# TheStaticTurtle_oshw-sdi3g-fiber__schema.net
KiCad netlist of a schematic drawn in Altium Designer
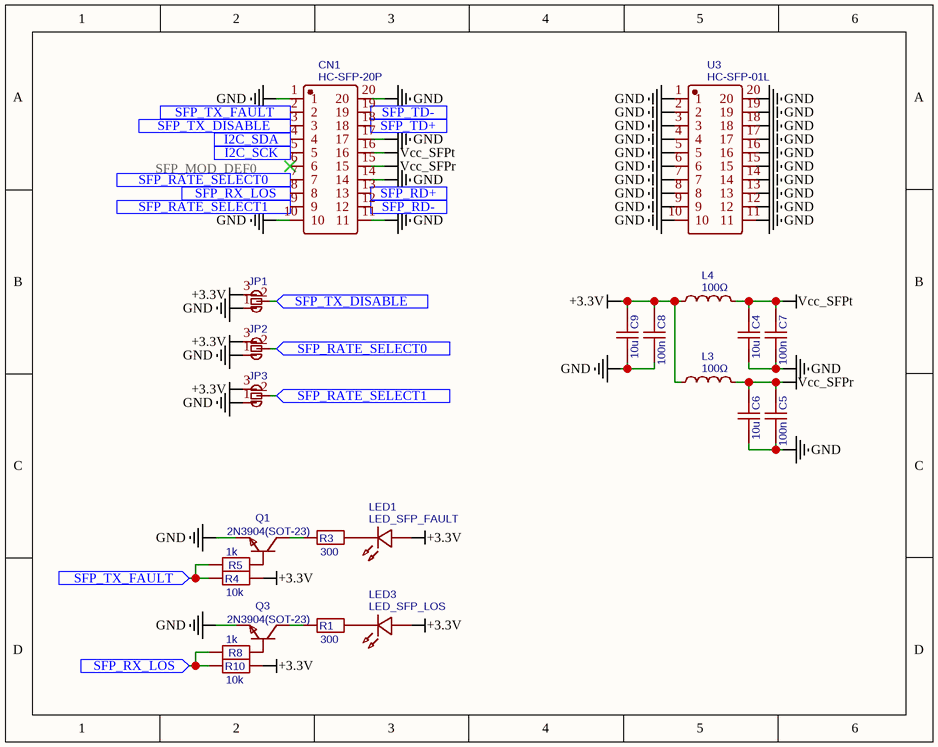
[diagram p0: TheStaticTurtle_oshw-sdi3g-fiber__schematic_V4-Reclocked_OSHW_BiDi_SDI_Fiber_Converter_V4_Reclocker_2024-11-17__SFP.schdoc]

(export (version "E")
  (design (tool "Eeschema 10.0.6"))
  (components
    (comp (ref "C4")
      (value "10u")
      (fields (field (name "CONTRIBUTOR") "LCEDA_Lib"))
      (libsource (lib "altium-import") (part "root_1_10u_"))
    )
    (comp (ref "C5")
      (value "100n")
      (fields (field (name "CONTRIBUTOR") "LCEDA_Lib"))
      (libsource (lib "altium-import") (part "root_1_100n_"))
    )
    (comp (ref "C6")
      (value "10u")
      (fields (field (name "CONTRIBUTOR") "LCEDA_Lib"))
      (libsource (lib "altium-import") (part "root_1_10u_"))
    )
    (comp (ref "C7")
      (value "100n")
      (fields (field (name "CONTRIBUTOR") "LCEDA_Lib"))
      (libsource (lib "altium-import") (part "root_1_100n_"))
    )
    (comp (ref "C8")
      (value "100n")
      (fields (field (name "CONTRIBUTOR") "LCEDA_Lib"))
      (libsource (lib "altium-import") (part "root_1_100n_"))
    )
    (comp (ref "C9")
      (value "10u")
      (fields (field (name "CONTRIBUTOR") "LCEDA_Lib"))
      (libsource (lib "altium-import") (part "root_1_10u_"))
    )
    (comp (ref "CN1")
      (value "HC-SFP-20P")
      (fields (field (name "MANUFACTURER") "HCTL(华灿天禄)") (field (name "CONTRIBUTOR") "LCSC"))
      (libsource (lib "altium-import") (part "root_0_HC-SFP-20P_"))
    )
    (comp (ref "JP1")
      (value "SOLDER BRIDGE 3P")
      (fields (field (name "CONTRIBUTOR") "TheStaticTurtle"))
      (libsource (lib "altium-import") (part "root_0_SOLDER BRIDGE 3P_"))
    )
    (comp (ref "JP2")
      (value "SOLDER BRIDGE 3P")
      (fields (field (name "CONTRIBUTOR") "TheStaticTurtle"))
      (libsource (lib "altium-import") (part "root_0_SOLDER BRIDGE 3P_"))
    )
    (comp (ref "JP3")
      (value "SOLDER BRIDGE 3P")
      (fields (field (name "CONTRIBUTOR") "TheStaticTurtle"))
      (libsource (lib "altium-import") (part "root_0_SOLDER BRIDGE 3P_"))
    )
    (comp (ref "L3")
      (value "100Ω")
      (fields (field (name "MANUFACTURER") "Sunlord(顺络)") (field (name "MANUFACTURER PART") "GZ2012D101TF"))
      (libsource (lib "altium-import") (part "root_0_100Ω_"))
    )
    (comp (ref "L4")
      (value "100Ω")
      (fields (field (name "MANUFACTURER") "Sunlord(顺络)") (field (name "MANUFACTURER PART") "GZ2012D101TF"))
      (libsource (lib "altium-import") (part "root_0_100Ω_"))
    )
    (comp (ref "LED1")
      (value "LED_SFP_FAULT")
      (fields
        (field (name "MANUFACTURER") "EVERLIGHT(台湾亿光)")
        (field (name "MANUFACTURER PART") "17-21SURC/S530-A3/TR8")
        (field (name "CONTRIBUTOR") "LCEDA_Lib")
      )
      (libsource (lib "altium-import") (part "root_2_LED_SFP_FAULT_"))
    )
    (comp (ref "LED3")
      (value "LED_SFP_LOS")
      (fields
        (field (name "MANUFACTURER") "EVERLIGHT(台湾亿光)")
        (field (name "MANUFACTURER PART") "17-21SURC/S530-A3/TR8")
        (field (name "CONTRIBUTOR") "LCEDA_Lib")
      )
      (libsource (lib "altium-import") (part "root_2_LED_SFP_LOS_"))
    )
    (comp (ref "Q1")
      (value "2N3904(SOT-23)")
      (fields
        (field (name "MANUFACTURER") "KEC")
        (field (name "MANUFACTURER PART") "2n3904S-RTK/PS")
        (field (name "CONTRIBUTOR") "LCEDA_Lib")
      )
      (libsource (lib "altium-import") (part "root_1_2N3904(SOT-23)_"))
    )
    (comp (ref "Q3")
      (value "2N3904(SOT-23)")
      (fields
        (field (name "MANUFACTURER") "KEC")
        (field (name "MANUFACTURER PART") "2n3904S-RTK/PS")
        (field (name "CONTRIBUTOR") "LCEDA_Lib")
      )
      (libsource (lib "altium-import") (part "root_1_2N3904(SOT-23)_"))
    )
    (comp (ref "R1")
      (value "300")
      (fields (field (name "CONTRIBUTOR") "LCEDA_Lib"))
      (libsource (lib "altium-import") (part "root_2_300_"))
    )
    (comp (ref "R3")
      (value "300")
      (fields (field (name "CONTRIBUTOR") "LCEDA_Lib"))
      (libsource (lib "altium-import") (part "root_2_300_"))
    )
    (comp (ref "R4")
      (value "10k")
      (fields (field (name "CONTRIBUTOR") "LCEDA_Lib"))
      (libsource (lib "altium-import") (part "root_2_10k_"))
    )
    (comp (ref "R5")
      (value "1k")
      (fields (field (name "CONTRIBUTOR") "LCEDA_Lib"))
      (libsource (lib "altium-import") (part "root_2_1k_"))
    )
    (comp (ref "R8")
      (value "1k")
      (fields (field (name "CONTRIBUTOR") "LCEDA_Lib"))
      (libsource (lib "altium-import") (part "root_2_1k_"))
    )
    (comp (ref "R10")
      (value "10k")
      (fields (field (name "CONTRIBUTOR") "LCEDA_Lib"))
      (libsource (lib "altium-import") (part "root_2_10k_"))
    )
    (comp (ref "U3")
      (value "HC-SFP-01L")
      (fields (field (name "MANUFACTURER") "HCTL(华灿天禄)") (field (name "CONTRIBUTOR") "LCSC"))
      (libsource (lib "altium-import") (part "root_0_HC-SFP-01L_"))
    )
  )
  (nets
    (net (code "1") (name "+3.3V") (class "Default")
      (node (ref "C8") (pin "2") (pinfunction "2_2") (pintype "passive"))
      (node (ref "C9") (pin "2") (pinfunction "2_2") (pintype "passive"))
      (node (ref "JP1") (pin "3") (pinfunction "B_3") (pintype "passive"))
      (node (ref "JP2") (pin "3") (pinfunction "B_3") (pintype "passive"))
      (node (ref "JP3") (pin "3") (pinfunction "B_3") (pintype "passive"))
      (node (ref "L3") (pin "1") (pinfunction "1_1") (pintype "passive"))
      (node (ref "L4") (pin "1") (pinfunction "1_1") (pintype "passive"))
      (node (ref "LED1") (pin "1") (pinfunction "1_1") (pintype "passive"))
      (node (ref "LED3") (pin "1") (pinfunction "1_1") (pintype "passive"))
      (node (ref "R10") (pin "1") (pinfunction "1_1") (pintype "passive"))
      (node (ref "R4") (pin "1") (pinfunction "1_1") (pintype "passive"))
    )
    (net (code "2") (name "/I2C_SCK") (class "Default")
      (node (ref "CN1") (pin "5") (pinfunction "5_5") (pintype "passive"))
    )
    (net (code "3") (name "/I2C_SDA") (class "Default")
      (node (ref "CN1") (pin "4") (pinfunction "4_4") (pintype "passive"))
    )
    (net (code "4") (name "/SFP_RATE_SELECT0") (class "Default")
      (node (ref "CN1") (pin "7") (pinfunction "7_7") (pintype "passive"))
      (node (ref "JP2") (pin "2") (pinfunction "B_2") (pintype "passive"))
    )
    (net (code "5") (name "/SFP_RATE_SELECT1") (class "Default")
      (node (ref "CN1") (pin "9") (pinfunction "9_9") (pintype "passive"))
      (node (ref "JP3") (pin "2") (pinfunction "B_2") (pintype "passive"))
    )
    (net (code "6") (name "/SFP_RD+") (class "Default")
      (node (ref "CN1") (pin "13") (pinfunction "13_13") (pintype "passive"))
    )
    (net (code "7") (name "/SFP_RD-") (class "Default")
      (node (ref "CN1") (pin "12") (pinfunction "12_12") (pintype "passive"))
    )
    (net (code "8") (name "/SFP_RX_LOS") (class "Default")
      (node (ref "CN1") (pin "8") (pinfunction "8_8") (pintype "passive"))
      (node (ref "R10") (pin "2") (pinfunction "2_2") (pintype "passive"))
      (node (ref "R8") (pin "2") (pinfunction "2_2") (pintype "passive"))
    )
    (net (code "9") (name "/SFP_TD+") (class "Default")
      (node (ref "CN1") (pin "18") (pinfunction "18_18") (pintype "passive"))
    )
    (net (code "10") (name "/SFP_TD-") (class "Default")
      (node (ref "CN1") (pin "19") (pinfunction "19_19") (pintype "passive"))
    )
    (net (code "11") (name "/SFP_TX_DISABLE") (class "Default")
      (node (ref "CN1") (pin "3") (pinfunction "3_3") (pintype "passive"))
      (node (ref "JP1") (pin "2") (pinfunction "B_2") (pintype "passive"))
    )
    (net (code "12") (name "/SFP_TX_FAULT") (class "Default")
      (node (ref "CN1") (pin "2") (pinfunction "2_2") (pintype "passive"))
      (node (ref "R4") (pin "2") (pinfunction "2_2") (pintype "passive"))
      (node (ref "R5") (pin "2") (pinfunction "2_2") (pintype "passive"))
    )
    (net (code "13") (name "GND") (class "Default")
      (node (ref "C4") (pin "1") (pinfunction "1_1") (pintype "passive"))
      (node (ref "C5") (pin "1") (pinfunction "1_1") (pintype "passive"))
      (node (ref "C6") (pin "1") (pinfunction "1_1") (pintype "passive"))
      (node (ref "C7") (pin "1") (pinfunction "1_1") (pintype "passive"))
      (node (ref "C8") (pin "1") (pinfunction "1_1") (pintype "passive"))
      (node (ref "C9") (pin "1") (pinfunction "1_1") (pintype "passive"))
      (node (ref "CN1") (pin "1") (pinfunction "1_1") (pintype "passive"))
      (node (ref "CN1") (pin "10") (pinfunction "10_10") (pintype "passive"))
      (node (ref "CN1") (pin "11") (pinfunction "11_11") (pintype "passive"))
      (node (ref "CN1") (pin "14") (pinfunction "14_14") (pintype "passive"))
      (node (ref "CN1") (pin "17") (pinfunction "17_17") (pintype "passive"))
      (node (ref "CN1") (pin "20") (pinfunction "20_20") (pintype "passive"))
      (node (ref "JP1") (pin "1") (pinfunction "A_1") (pintype "passive"))
      (node (ref "JP2") (pin "1") (pinfunction "A_1") (pintype "passive"))
      (node (ref "JP3") (pin "1") (pinfunction "A_1") (pintype "passive"))
      (node (ref "Q1") (pin "1") (pinfunction "E_1") (pintype "passive"))
      (node (ref "Q3") (pin "1") (pinfunction "E_1") (pintype "passive"))
      (node (ref "U3") (pin "1") (pinfunction "1_1") (pintype "passive"))
      (node (ref "U3") (pin "10") (pinfunction "10_10") (pintype "passive"))
      (node (ref "U3") (pin "11") (pinfunction "11_11") (pintype "passive"))
      (node (ref "U3") (pin "12") (pinfunction "12_12") (pintype "passive"))
      (node (ref "U3") (pin "13") (pinfunction "13_13") (pintype "passive"))
      (node (ref "U3") (pin "14") (pinfunction "14_14") (pintype "passive"))
      (node (ref "U3") (pin "15") (pinfunction "15_15") (pintype "passive"))
      (node (ref "U3") (pin "16") (pinfunction "16_16") (pintype "passive"))
      (node (ref "U3") (pin "17") (pinfunction "17_17") (pintype "passive"))
      (node (ref "U3") (pin "18") (pinfunction "18_18") (pintype "passive"))
      (node (ref "U3") (pin "19") (pinfunction "19_19") (pintype "passive"))
      (node (ref "U3") (pin "2") (pinfunction "2_2") (pintype "passive"))
      (node (ref "U3") (pin "20") (pinfunction "20_20") (pintype "passive"))
      (node (ref "U3") (pin "3") (pinfunction "3_3") (pintype "passive"))
      (node (ref "U3") (pin "4") (pinfunction "4_4") (pintype "passive"))
      (node (ref "U3") (pin "5") (pinfunction "5_5") (pintype "passive"))
      (node (ref "U3") (pin "6") (pinfunction "6_6") (pintype "passive"))
      (node (ref "U3") (pin "7") (pinfunction "7_7") (pintype "passive"))
      (node (ref "U3") (pin "8") (pinfunction "8_8") (pintype "passive"))
      (node (ref "U3") (pin "9") (pinfunction "9_9") (pintype "passive"))
    )
    (net (code "14") (name "Net-(LED1-Pad2)") (class "Default")
      (node (ref "LED1") (pin "2") (pinfunction "2_2") (pintype "passive"))
      (node (ref "R3") (pin "1") (pinfunction "1_1") (pintype "passive"))
    )
    (net (code "15") (name "Net-(LED3-Pad2)") (class "Default")
      (node (ref "LED3") (pin "2") (pinfunction "2_2") (pintype "passive"))
      (node (ref "R1") (pin "1") (pinfunction "1_1") (pintype "passive"))
    )
    (net (code "16") (name "Net-(Q1-B)") (class "Default")
      (node (ref "Q1") (pin "2") (pinfunction "B_2") (pintype "passive"))
      (node (ref "R5") (pin "1") (pinfunction "1_1") (pintype "passive"))
    )
    (net (code "17") (name "Net-(Q1-C)") (class "Default")
      (node (ref "Q1") (pin "3") (pinfunction "C_3") (pintype "passive"))
      (node (ref "R3") (pin "2") (pinfunction "2_2") (pintype "passive"))
    )
    (net (code "18") (name "Net-(Q3-B)") (class "Default")
      (node (ref "Q3") (pin "2") (pinfunction "B_2") (pintype "passive"))
      (node (ref "R8") (pin "1") (pinfunction "1_1") (pintype "passive"))
    )
    (net (code "19") (name "Net-(Q3-C)") (class "Default")
      (node (ref "Q3") (pin "3") (pinfunction "C_3") (pintype "passive"))
      (node (ref "R1") (pin "2") (pinfunction "2_2") (pintype "passive"))
    )
    (net (code "20") (name "Vcc_SFPr") (class "Default")
      (node (ref "C5") (pin "2") (pinfunction "2_2") (pintype "passive"))
      (node (ref "C6") (pin "2") (pinfunction "2_2") (pintype "passive"))
      (node (ref "CN1") (pin "15") (pinfunction "15_15") (pintype "passive"))
      (node (ref "L3") (pin "2") (pinfunction "2_2") (pintype "passive"))
    )
    (net (code "21") (name "Vcc_SFPt") (class "Default")
      (node (ref "C4") (pin "2") (pinfunction "2_2") (pintype "passive"))
      (node (ref "C7") (pin "2") (pinfunction "2_2") (pintype "passive"))
      (node (ref "CN1") (pin "16") (pinfunction "16_16") (pintype "passive"))
      (node (ref "L4") (pin "2") (pinfunction "2_2") (pintype "passive"))
    )
    (net (code "22") (name "unconnected-(CN1-Pad6)") (class "Default")
      (node (ref "CN1") (pin "6") (pinfunction "6_6") (pintype "passive+no_connect"))
    )
  )
)
